# 3_Communication.net
KiCad netlist of a schematic drawn in Altium Designer
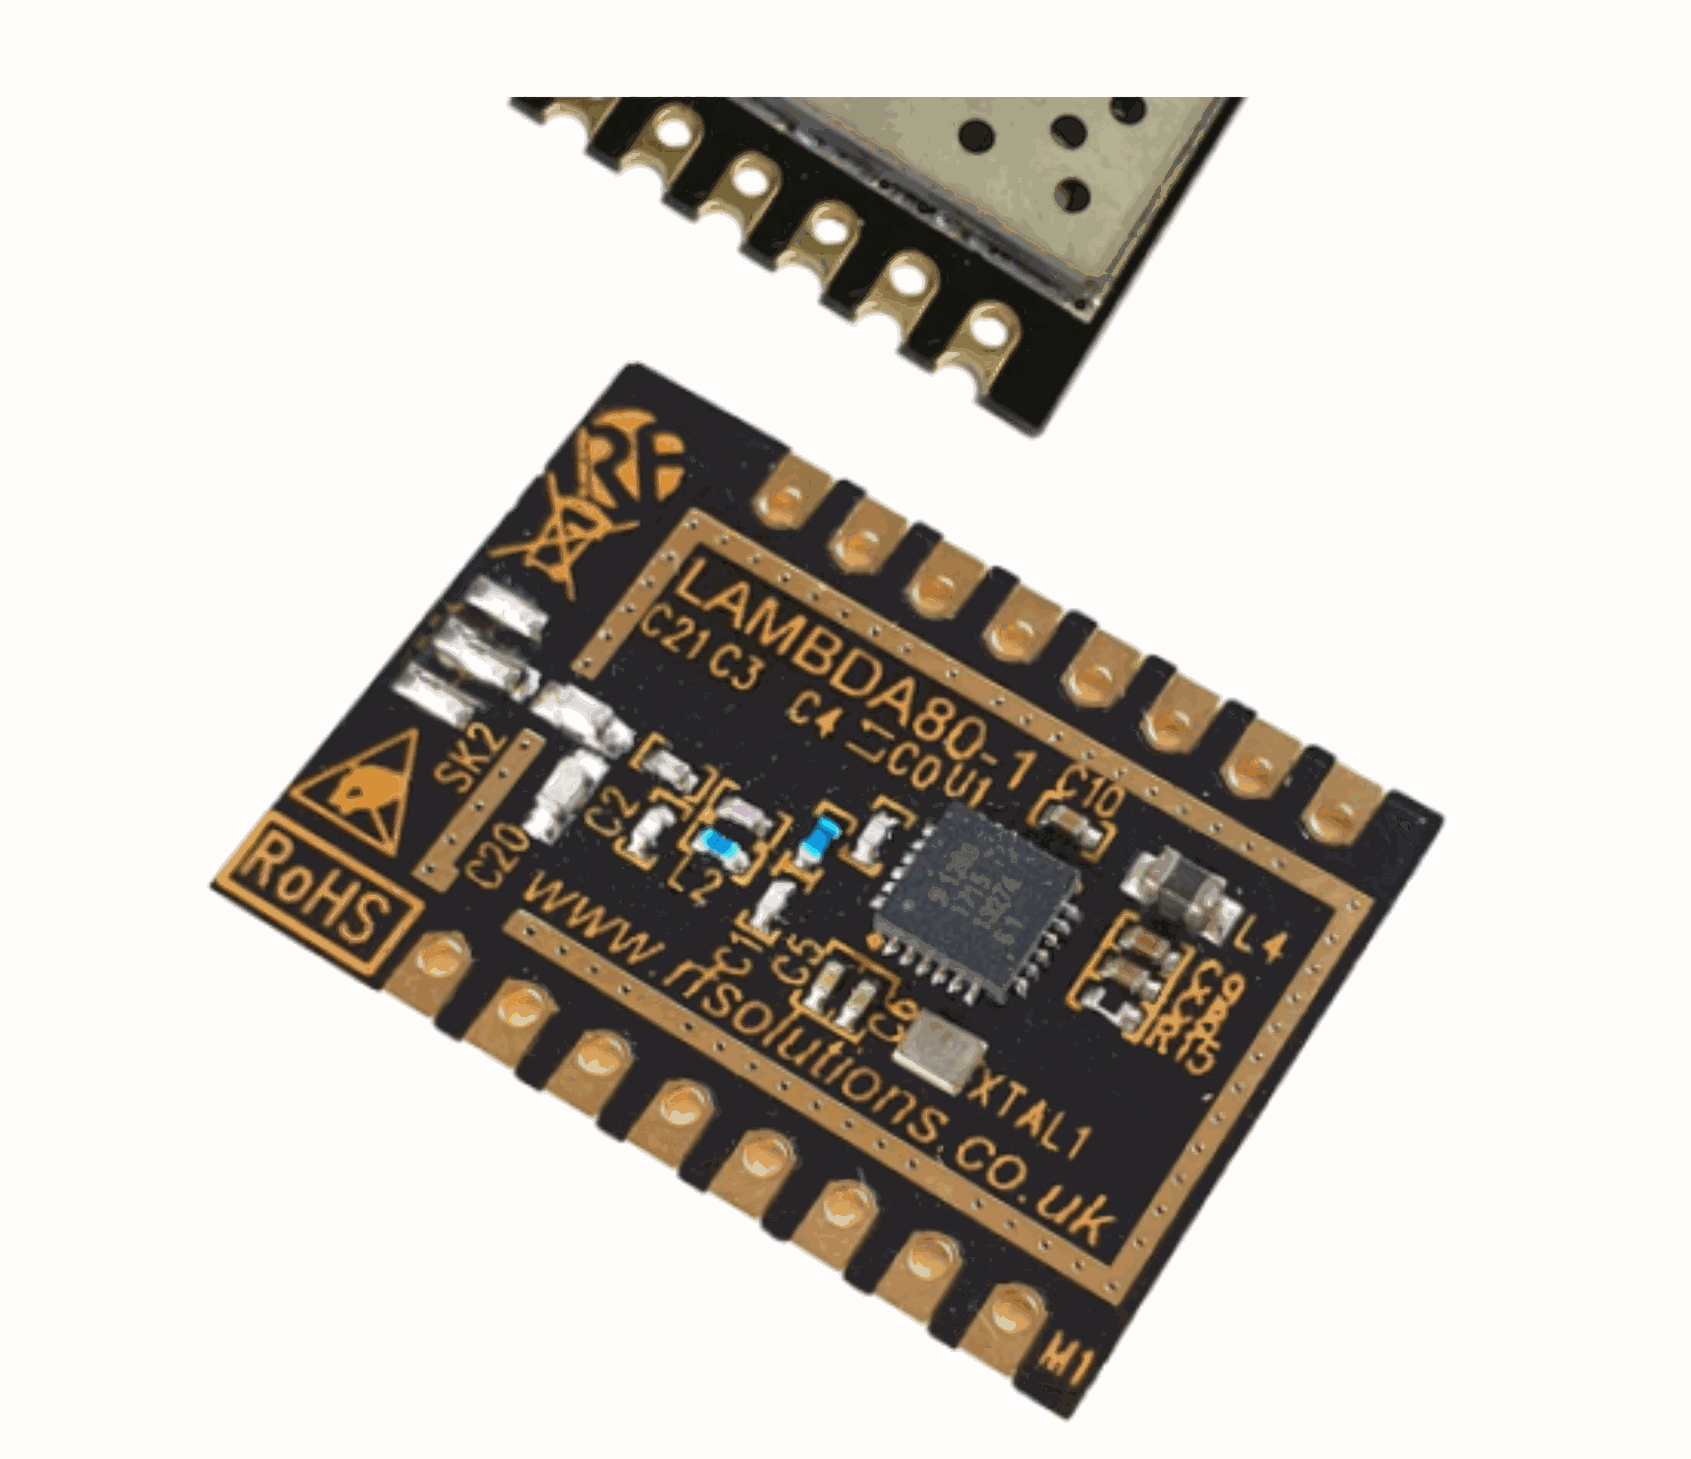
[diagram p0: 3_Communication.SchDoc, top middle]
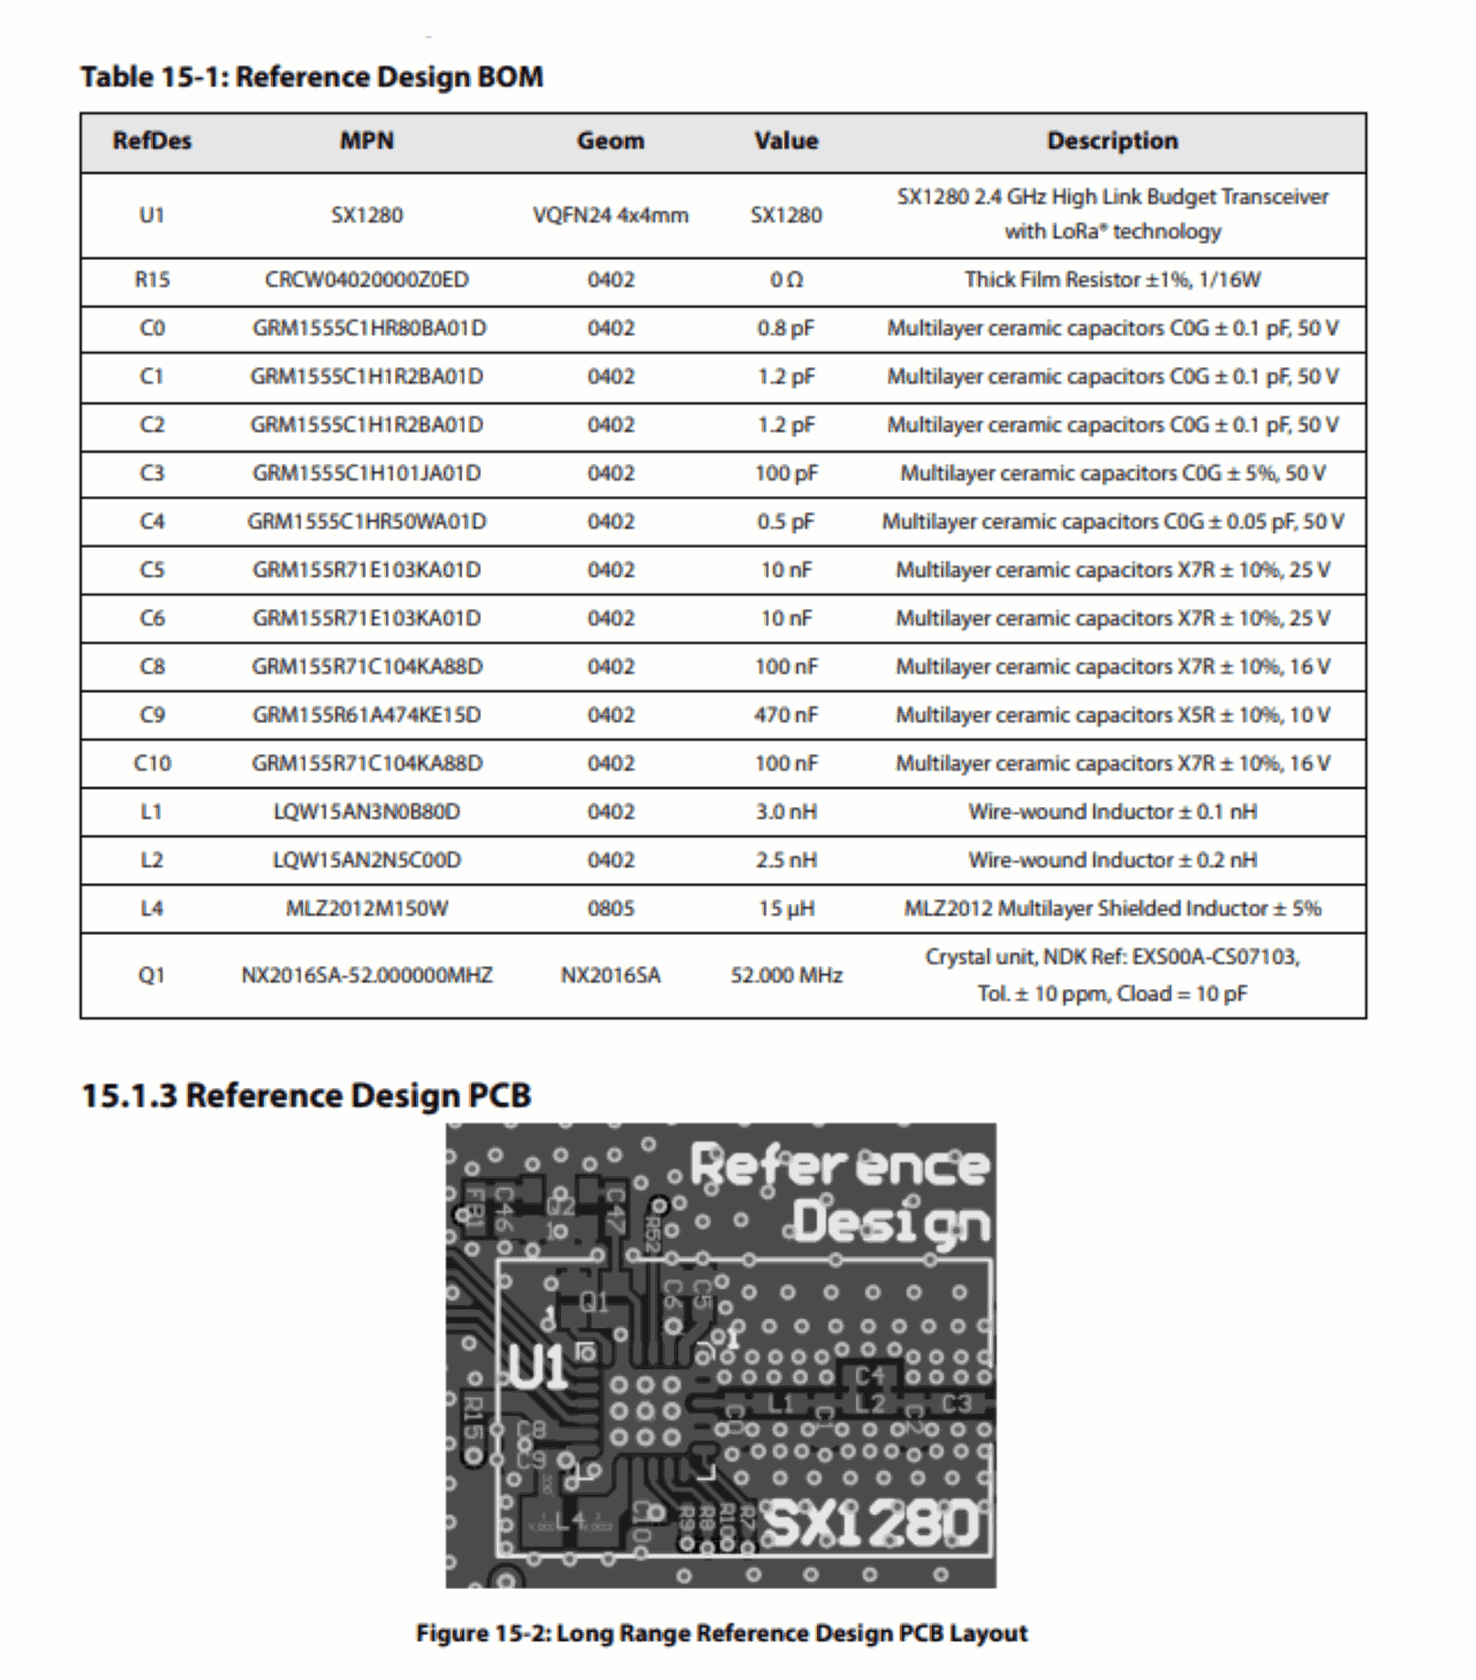
[diagram p1: 3_Communication.SchDoc, top right]
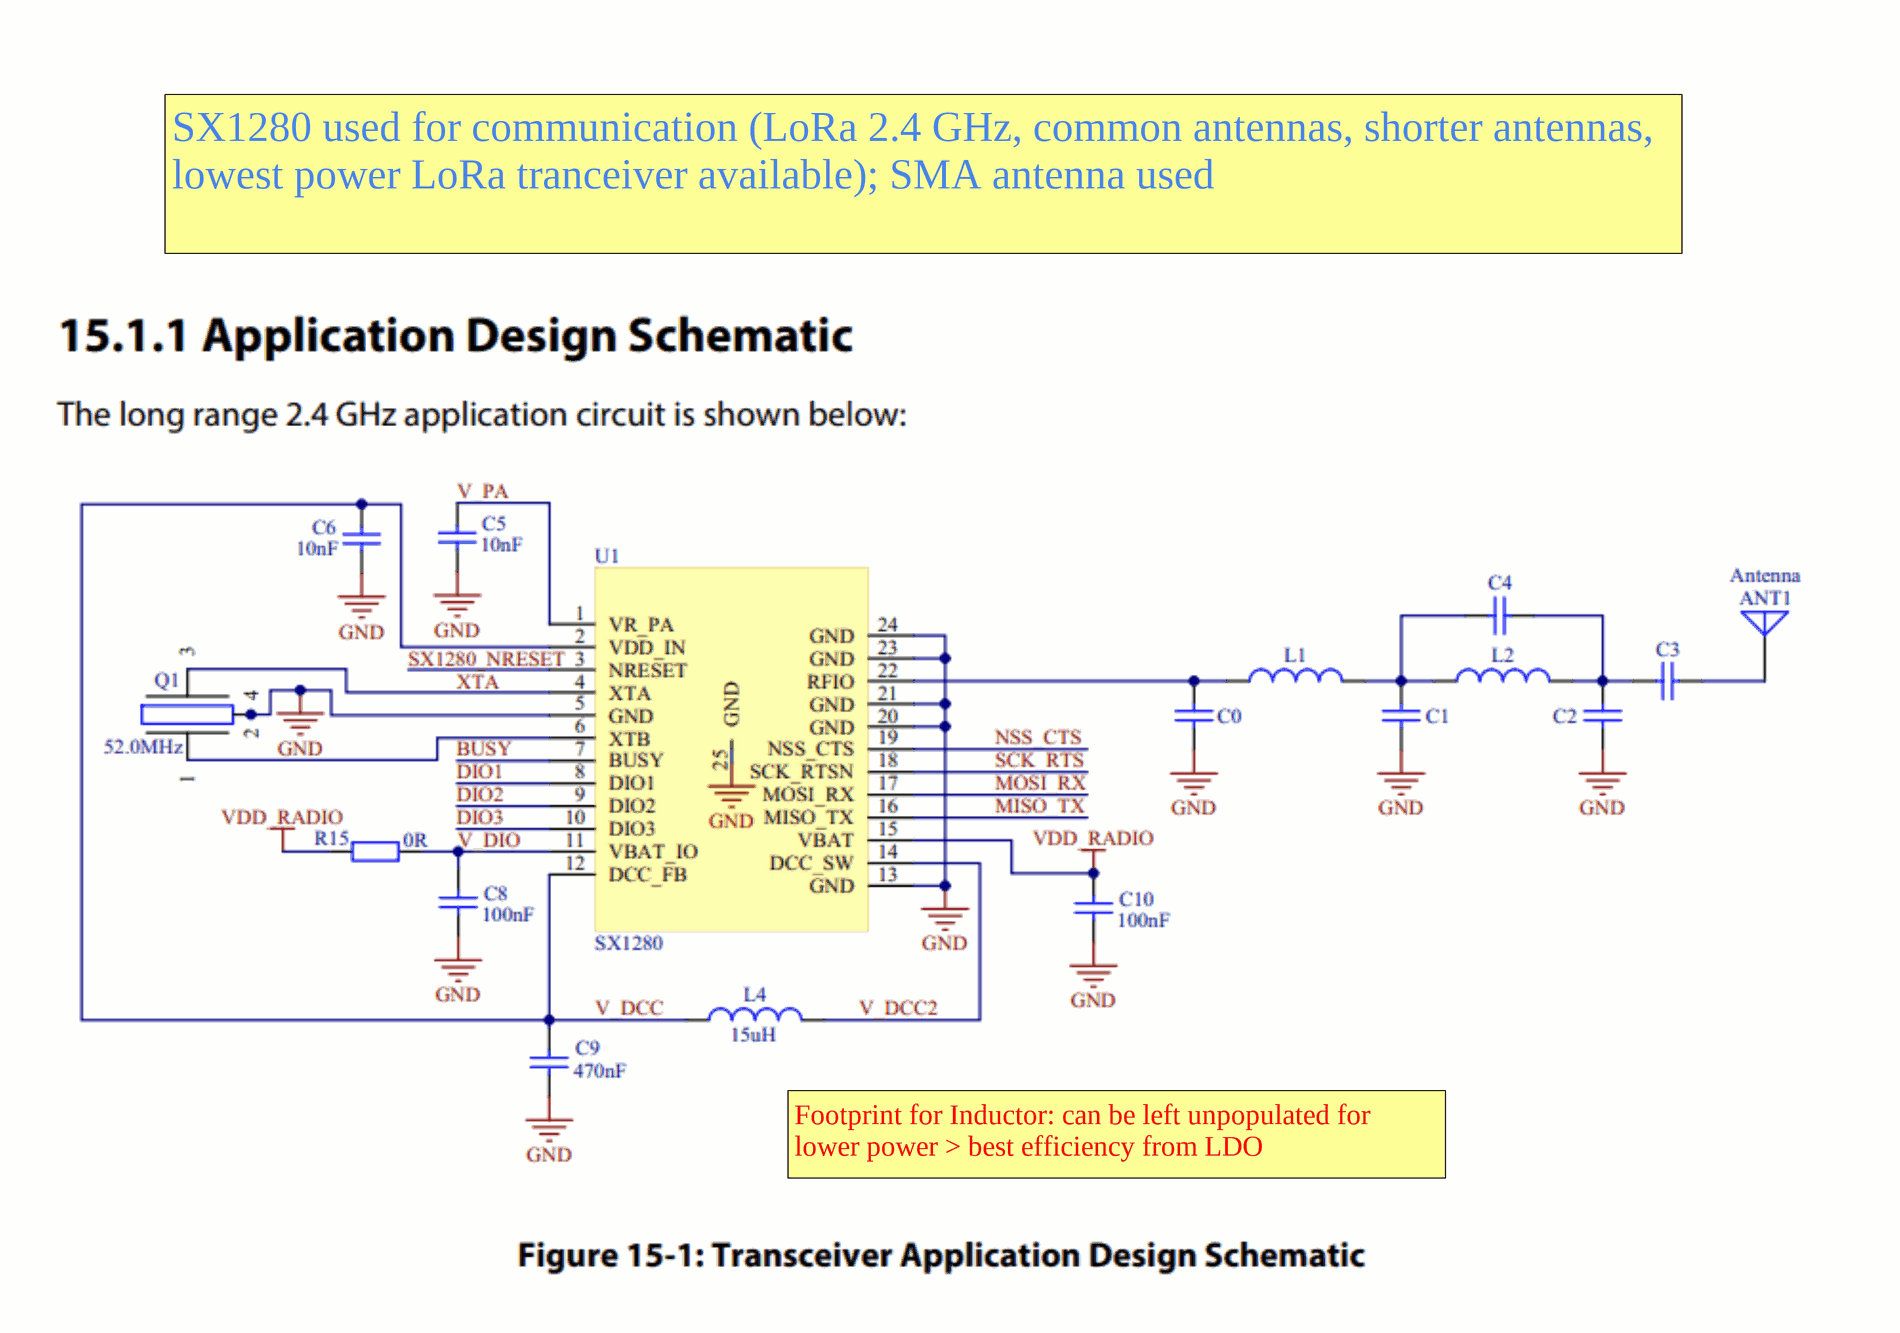
[diagram p2: 3_Communication.SchDoc, bottom left]
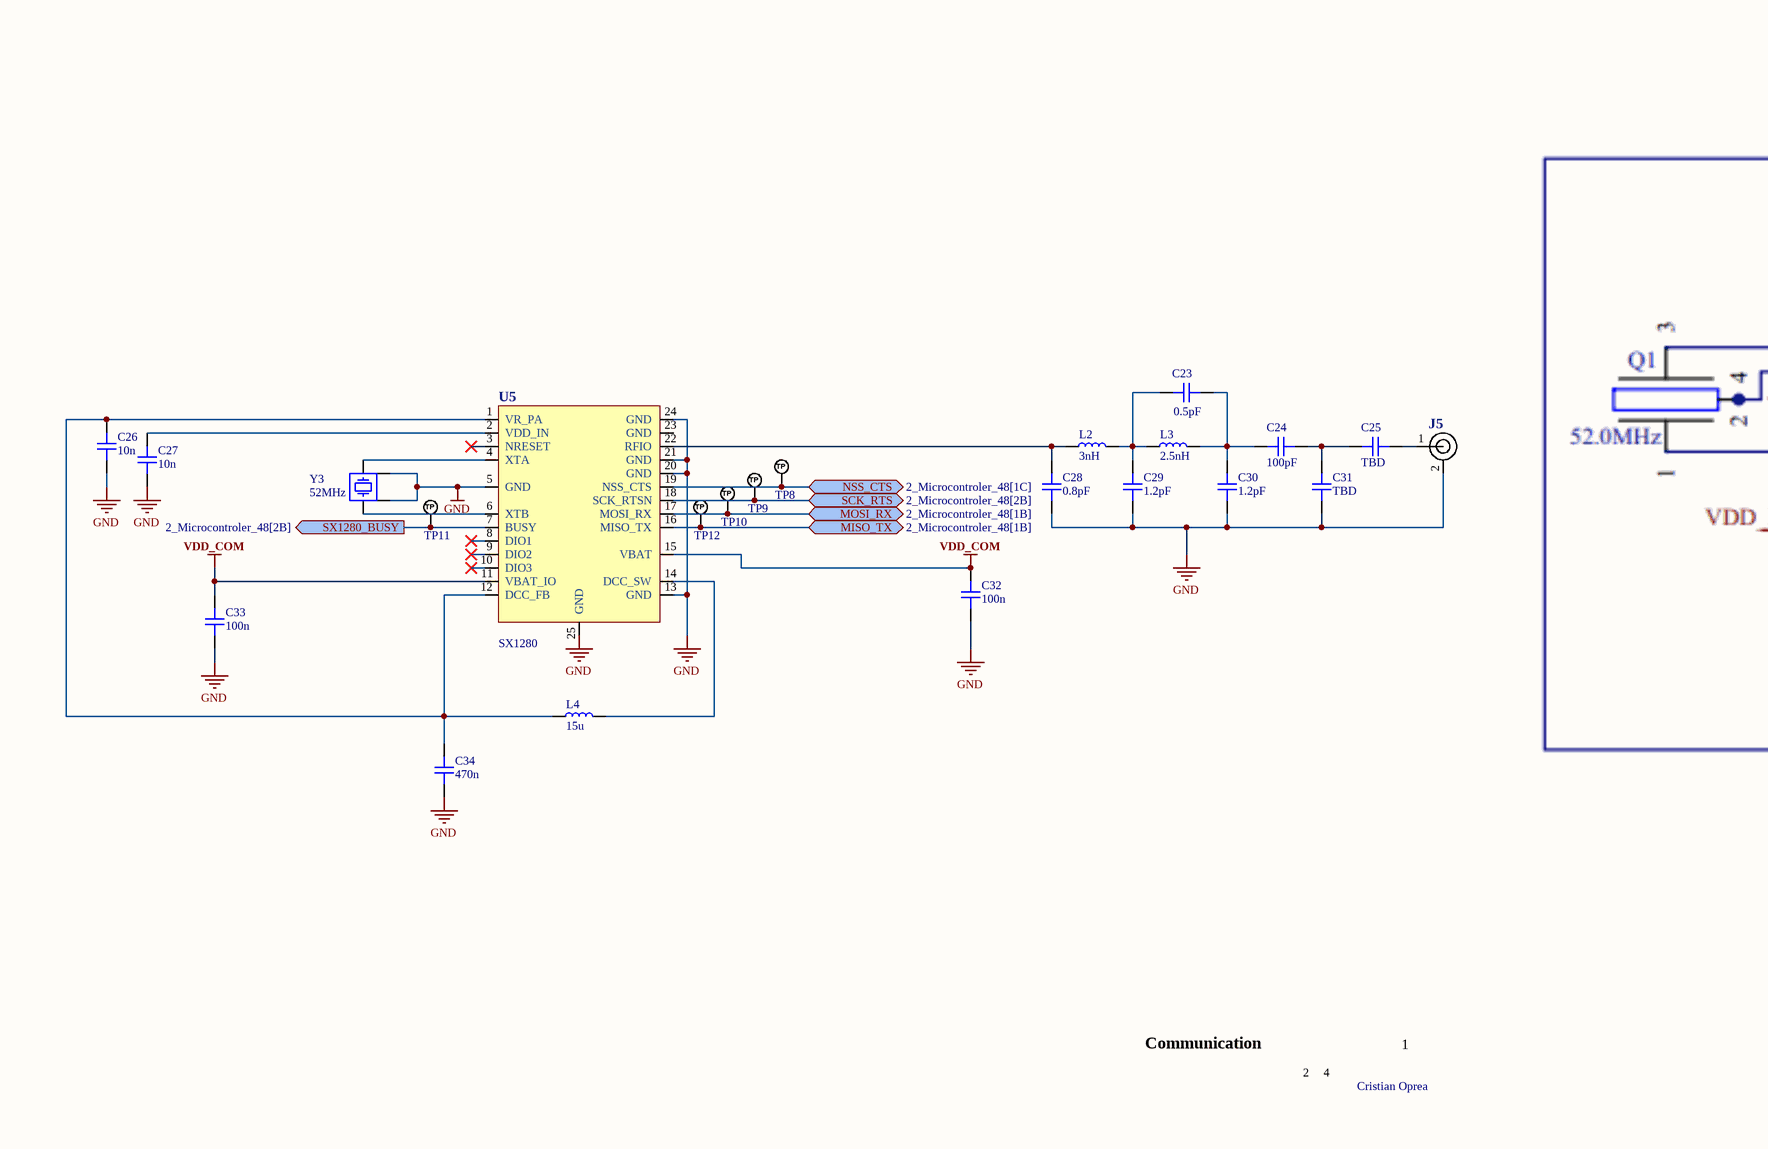
[diagram p3: 3_Communication.SchDoc, bottom middle]
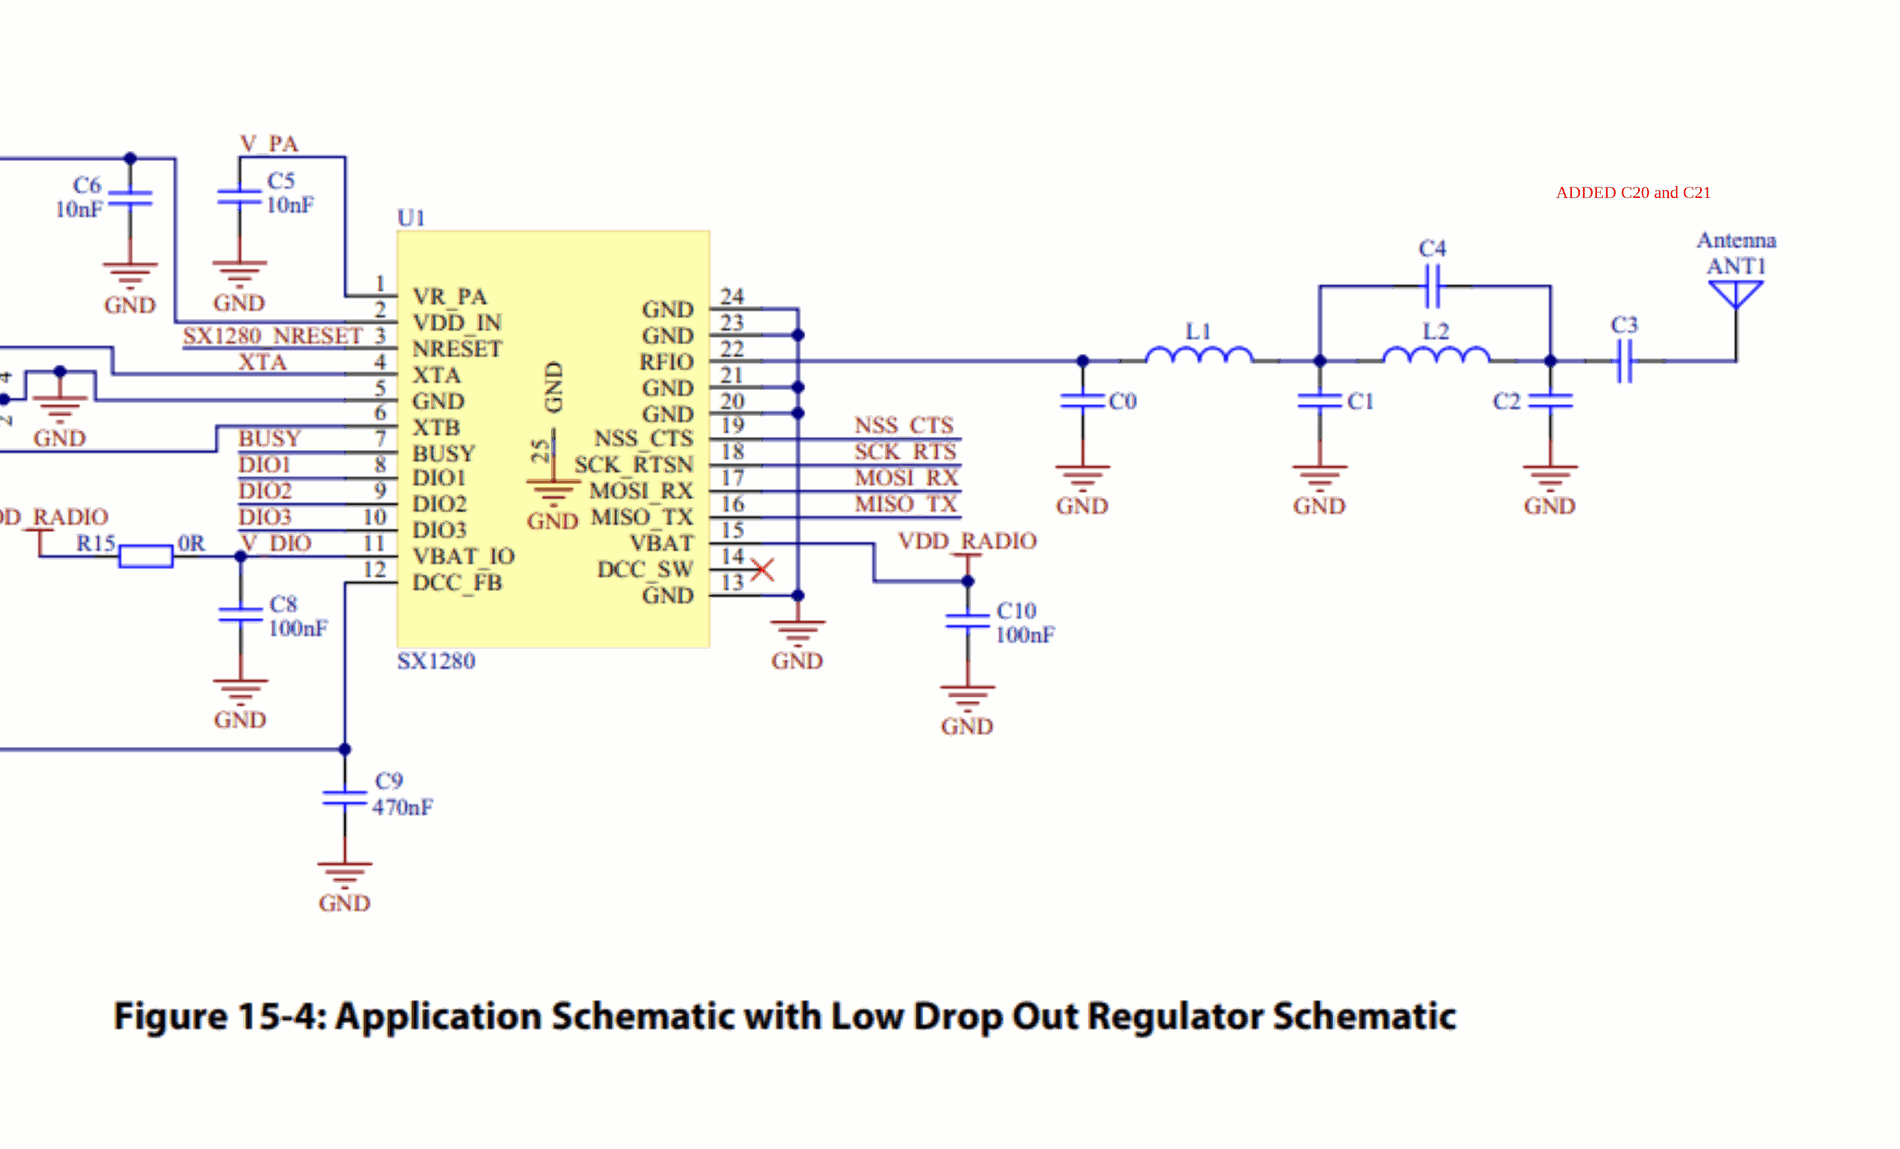
[diagram p4: 3_Communication.SchDoc, bottom right]

(export (version "E")
  (design (tool "Eeschema 10.0.6"))
  (components
    (comp (ref "C23")
      (value "0.5pF")
      (footprint "C0603")
      (description "Capacitor SMD 0603")
      (libsource (lib "Schlib_H2") (part "CAP_0603"))
    )
    (comp (ref "C24")
      (value "100pF")
      (footprint "C0603")
      (description "Capacitor SMD 0603")
      (libsource (lib "Schlib_H2") (part "CAP_0603"))
    )
    (comp (ref "C25")
      (value "TBD")
      (footprint "C0805")
      (description "Capacitor SMD 0805")
      (libsource (lib "Schlib_H2") (part "CAP_0603"))
    )
    (comp (ref "C26")
      (value "10n")
      (footprint "C0603")
      (description "Capacitor SMD 0603")
      (libsource (lib "Schlib_H2") (part "CAP_0603"))
    )
    (comp (ref "C27")
      (value "10n")
      (footprint "C0603")
      (description "Capacitor SMD 0603")
      (libsource (lib "Schlib_H2") (part "CAP_0603"))
    )
    (comp (ref "C28")
      (value "0.8pF")
      (footprint "C0603")
      (description "Capacitor SMD 0805")
      (libsource (lib "Schlib_H2") (part "CAP_0805"))
    )
    (comp (ref "C29")
      (value "1.2pF")
      (footprint "C0603")
      (description "Capacitor SMD 0603")
      (libsource (lib "Schlib_H2") (part "CAP_0603"))
    )
    (comp (ref "C30")
      (value "1.2pF")
      (footprint "C0603")
      (description "Capacitor SMD 0603")
      (libsource (lib "Schlib_H2") (part "CAP_0603"))
    )
    (comp (ref "C31")
      (value "TBD")
      (footprint "C0805")
      (description "Capacitor SMD 0805")
      (libsource (lib "Schlib_H2") (part "CAP_0603"))
    )
    (comp (ref "C32")
      (value "100n")
      (footprint "C0603")
      (description "Capacitor SMD 0603")
      (libsource (lib "Schlib_H2") (part "CAP_0603"))
    )
    (comp (ref "C33")
      (value "100n")
      (footprint "C0603")
      (description "Capacitor SMD 0603")
      (libsource (lib "Schlib_H2") (part "CAP_0603"))
    )
    (comp (ref "C34")
      (value "470n")
      (footprint "C0603")
      (description "Capacitor SMD 0603")
      (libsource (lib "Schlib_H2") (part "CAP_0603"))
    )
    (comp (ref "J5")
      (value "SMA_EDGE_CONN")
      (footprint "CON_SMA-EDGE-S")
      (description "RF Connector SMA Female 50 Ohms 18 GHz PCB Edge Mount")
      (fields
        (field (name "MANUFACTURER") "RF Solutions")
        (field (name "MANUFACTURER PART NUMBER") "CON-SMA-EDGE-S")
      )
      (libsource (lib "Schlib_H2") (part "CON-SMA-EDGE-S"))
    )
    (comp (ref "L2")
      (value "3nH")
      (footprint "R0603")
      (description "Inductor SMD 0603")
      (libsource (lib "Schlib_H2") (part "IND_0603"))
    )
    (comp (ref "L3")
      (value "2.5nH")
      (footprint "R0603")
      (description "Inductor SMD 0603")
      (libsource (lib "Schlib_H2") (part "IND_0603"))
    )
    (comp (ref "L4")
      (value "15u")
      (footprint "IND_3.2_4")
      (description "Inductor SMD 0603")
      (libsource (lib "Schlib_H2") (part "IND_0603"))
    )
    (comp (ref "TP8")
      (value "TP_NOBOM")
      (footprint "TEST_PAD_THD")
      (description "Test Point Round 1mm (NO BOM)")
      (libsource (lib "Schlib_H2") (part "TEST_POINT_RND_1MM"))
    )
    (comp (ref "TP9")
      (value "TP_NOBOM")
      (footprint "TEST_PAD_THD")
      (description "Test Point Round 1mm (NO BOM)")
      (libsource (lib "Schlib_H2") (part "TEST_POINT_RND_1MM"))
    )
    (comp (ref "TP10")
      (value "TP_NOBOM")
      (footprint "TEST_PAD_THD")
      (description "Test Point Round 1mm (NO BOM)")
      (libsource (lib "Schlib_H2") (part "TEST_POINT_RND_1MM"))
    )
    (comp (ref "TP11")
      (value "TP_NOBOM")
      (footprint "TEST_PAD_THD")
      (description "Test Point Round 1mm (NO BOM)")
      (libsource (lib "Schlib_H2") (part "TEST_POINT_RND_1MM"))
    )
    (comp (ref "TP12")
      (value "TP_NOBOM")
      (footprint "TEST_PAD_THD")
      (description "Test Point Round 1mm (NO BOM)")
      (libsource (lib "Schlib_H2") (part "TEST_POINT_RND_1MM"))
    )
    (comp (ref "U5")
      (value "SX1280")
      (footprint "QFN-24_4x4_0.5")
      (description "Low power LoRa transceiver operating at 2.4GHz with ranging capability")
      (libsource (lib "Schlib_H2") (part "SX1280"))
    )
    (comp (ref "Y3")
      (value "52MHz")
      (footprint "CRYSTAL_2016_4P")
      (description "Crystal")
      (fields
        (field (name "MANUFACTURER") "Epson")
        (field (name "MANUFACTURER PART NUMBER") "TSX-3225 24.0000MF15X-AC")
      )
      (libsource (lib "Schlib_H2") (part "Crystal"))
    )
  )
  (nets
    (net (code "1") (name "/MISO_TX") (class "Default")
      (node (ref "TP12") (pin "1") (pinfunction "TP_1") (pintype "passive"))
      (node (ref "U5") (pin "16") (pinfunction "MISO_TX_16") (pintype "passive"))
    )
    (net (code "2") (name "/MOSI_RX") (class "Default")
      (node (ref "TP10") (pin "1") (pinfunction "TP_1") (pintype "passive"))
      (node (ref "U5") (pin "17") (pinfunction "MOSI_RX_17") (pintype "passive"))
    )
    (net (code "3") (name "/NSS_CTS") (class "Default")
      (node (ref "TP8") (pin "1") (pinfunction "TP_1") (pintype "passive"))
      (node (ref "U5") (pin "19") (pinfunction "NSS_CTS_19") (pintype "passive"))
    )
    (net (code "4") (name "/SCK_RTS") (class "Default")
      (node (ref "TP9") (pin "1") (pinfunction "TP_1") (pintype "passive"))
      (node (ref "U5") (pin "18") (pinfunction "SCK_RTSN_18") (pintype "passive"))
    )
    (net (code "5") (name "/SX1280_BUSY") (class "Default")
      (node (ref "TP11") (pin "1") (pinfunction "TP_1") (pintype "passive"))
      (node (ref "U5") (pin "7") (pinfunction "BUSY_7") (pintype "passive"))
    )
    (net (code "6") (name "GND") (class "Default")
      (node (ref "C26") (pin "1") (pinfunction "1_1") (pintype "passive"))
      (node (ref "C27") (pin "1") (pinfunction "1_1") (pintype "passive"))
      (node (ref "C28") (pin "1") (pinfunction "1_1") (pintype "passive"))
      (node (ref "C29") (pin "1") (pinfunction "1_1") (pintype "passive"))
      (node (ref "C30") (pin "1") (pinfunction "1_1") (pintype "passive"))
      (node (ref "C31") (pin "1") (pinfunction "1_1") (pintype "passive"))
      (node (ref "C32") (pin "1") (pinfunction "1_1") (pintype "passive"))
      (node (ref "C33") (pin "1") (pinfunction "1_1") (pintype "passive"))
      (node (ref "C34") (pin "1") (pinfunction "1_1") (pintype "passive"))
      (node (ref "J5") (pin "2") (pinfunction "2_2") (pintype "passive"))
      (node (ref "U5") (pin "13") (pinfunction "GND_13") (pintype "passive"))
      (node (ref "U5") (pin "20") (pinfunction "GND_20") (pintype "passive"))
      (node (ref "U5") (pin "21") (pinfunction "GND_21") (pintype "passive"))
      (node (ref "U5") (pin "24") (pinfunction "GND_24") (pintype "passive"))
      (node (ref "U5") (pin "25") (pinfunction "GND_25") (pintype "passive"))
      (node (ref "U5") (pin "5") (pinfunction "GND_5") (pintype "passive"))
      (node (ref "Y3") (pin "2") (pinfunction "2_2") (pintype "passive"))
      (node (ref "Y3") (pin "4") (pinfunction "4_4") (pintype "passive"))
    )
    (net (code "7") (name "Net-(C23-Pad1)") (class "Default")
      (node (ref "C23") (pin "1") (pinfunction "1_1") (pintype "passive"))
      (node (ref "C24") (pin "2") (pinfunction "2_2") (pintype "passive"))
      (node (ref "C30") (pin "2") (pinfunction "2_2") (pintype "passive"))
      (node (ref "L3") (pin "2") (pinfunction "2_2") (pintype "passive"))
    )
    (net (code "8") (name "Net-(C23-Pad2)") (class "Default")
      (node (ref "C23") (pin "2") (pinfunction "2_2") (pintype "passive"))
      (node (ref "C29") (pin "2") (pinfunction "2_2") (pintype "passive"))
      (node (ref "L2") (pin "2") (pinfunction "2_2") (pintype "passive"))
      (node (ref "L3") (pin "1") (pinfunction "1_1") (pintype "passive"))
    )
    (net (code "9") (name "Net-(C24-Pad1)") (class "Default")
      (node (ref "C24") (pin "1") (pinfunction "1_1") (pintype "passive"))
      (node (ref "C25") (pin "2") (pinfunction "2_2") (pintype "passive"))
      (node (ref "C31") (pin "2") (pinfunction "2_2") (pintype "passive"))
    )
    (net (code "10") (name "Net-(C25-Pad1)") (class "Default")
      (node (ref "C25") (pin "1") (pinfunction "1_1") (pintype "passive"))
      (node (ref "J5") (pin "1") (pinfunction "1_1") (pintype "passive"))
    )
    (net (code "11") (name "Net-(U5-DCC_FB)") (class "Default")
      (node (ref "C26") (pin "2") (pinfunction "2_2") (pintype "passive"))
      (node (ref "C34") (pin "2") (pinfunction "2_2") (pintype "passive"))
      (node (ref "L4") (pin "1") (pinfunction "1_1") (pintype "passive"))
      (node (ref "U5") (pin "1") (pinfunction "VR_PA_1") (pintype "passive"))
      (node (ref "U5") (pin "12") (pinfunction "DCC_FB_12") (pintype "passive"))
    )
    (net (code "12") (name "Net-(U5-DCC_SW)") (class "Default")
      (node (ref "L4") (pin "2") (pinfunction "2_2") (pintype "passive"))
      (node (ref "U5") (pin "14") (pinfunction "DCC_SW_14") (pintype "passive"))
    )
    (net (code "13") (name "Net-(U5-RFIO)") (class "Default")
      (node (ref "C28") (pin "2") (pinfunction "2_2") (pintype "passive"))
      (node (ref "L2") (pin "1") (pinfunction "1_1") (pintype "passive"))
      (node (ref "U5") (pin "22") (pinfunction "RFIO_22") (pintype "passive"))
    )
    (net (code "14") (name "Net-(U5-VDD_IN)") (class "Default")
      (node (ref "C27") (pin "2") (pinfunction "2_2") (pintype "passive"))
      (node (ref "U5") (pin "2") (pinfunction "VDD_IN_2") (pintype "passive"))
    )
    (net (code "15") (name "Net-(U5-XTA)") (class "Default")
      (node (ref "U5") (pin "4") (pinfunction "XTA_4") (pintype "passive"))
      (node (ref "Y3") (pin "3") (pinfunction "3_3") (pintype "passive"))
    )
    (net (code "16") (name "Net-(U5-XTB)") (class "Default")
      (node (ref "U5") (pin "6") (pinfunction "XTB_6") (pintype "passive"))
      (node (ref "Y3") (pin "1") (pinfunction "1_1") (pintype "passive"))
    )
    (net (code "17") (name "VDD_COM") (class "Default")
      (node (ref "C32") (pin "2") (pinfunction "2_2") (pintype "passive"))
      (node (ref "C33") (pin "2") (pinfunction "2_2") (pintype "passive"))
      (node (ref "U5") (pin "11") (pinfunction "VBAT_IO_11") (pintype "passive"))
      (node (ref "U5") (pin "15") (pinfunction "VBAT_15") (pintype "passive"))
    )
    (net (code "18") (name "unconnected-(U5-DIO1-Pad8)") (class "Default")
      (node (ref "U5") (pin "8") (pinfunction "DIO1_8") (pintype "passive+no_connect"))
    )
    (net (code "19") (name "unconnected-(U5-DIO2-Pad9)") (class "Default")
      (node (ref "U5") (pin "9") (pinfunction "DIO2_9") (pintype "passive+no_connect"))
    )
    (net (code "20") (name "unconnected-(U5-DIO3-Pad10)") (class "Default")
      (node (ref "U5") (pin "10") (pinfunction "DIO3_10") (pintype "passive+no_connect"))
    )
    (net (code "21") (name "unconnected-(U5-GND-Pad23)") (class "Default")
      (node (ref "U5") (pin "23") (pinfunction "GND_23") (pintype "passive"))
    )
    (net (code "22") (name "unconnected-(U5-NRESET-Pad3)") (class "Default")
      (node (ref "U5") (pin "3") (pinfunction "NRESET_3") (pintype "passive+no_connect"))
    )
  )
)
